# Environmental_PCB_Group5.net
KiCad netlist of a schematic drawn in EasyEDA Pro
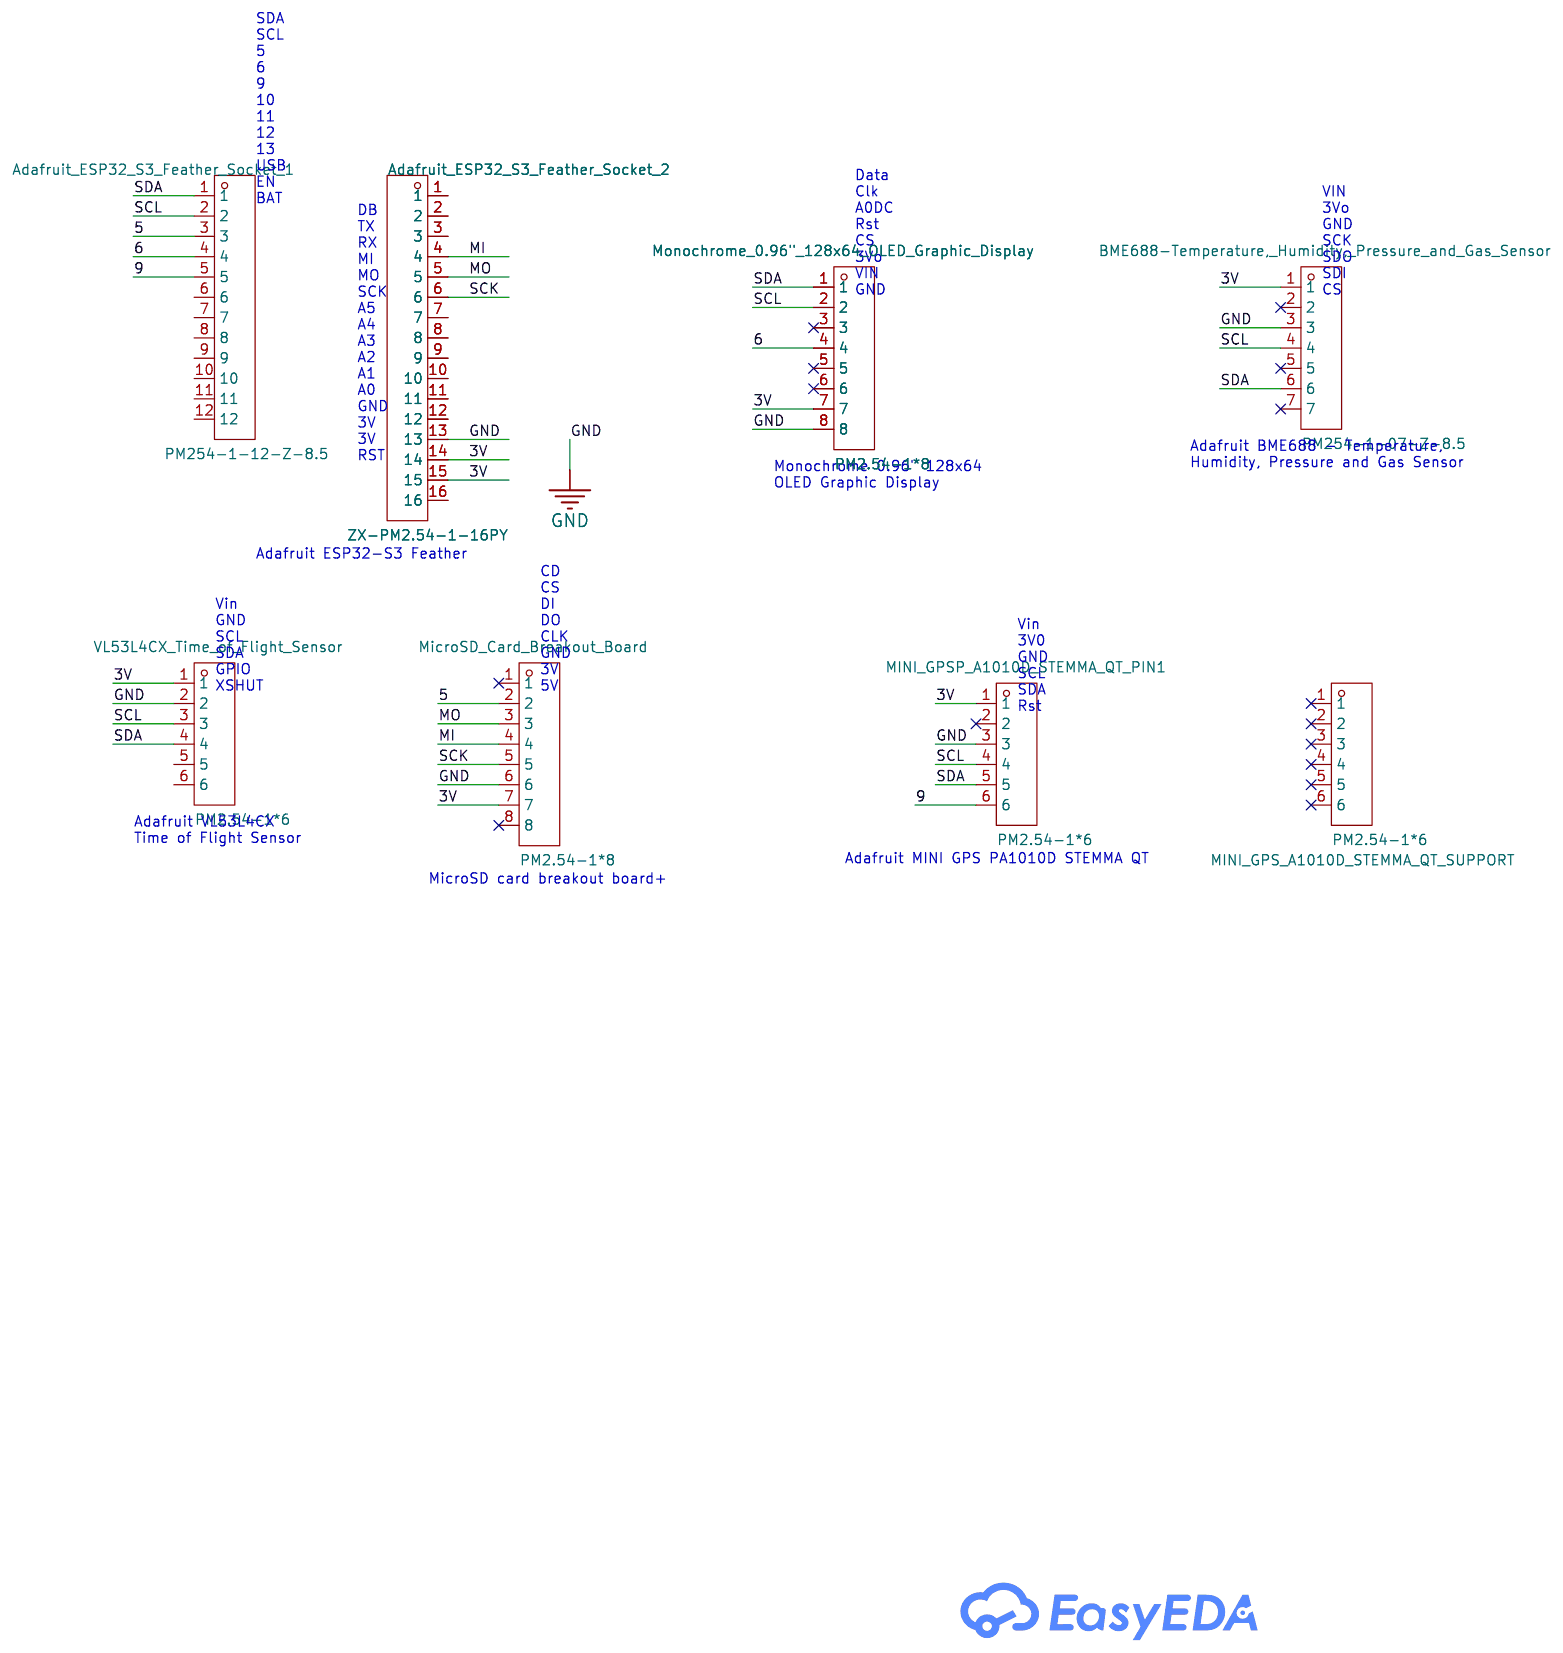
[diagram p0: schematic sheet]

(export (version "E")
  (design (tool "Eeschema 10.0.6"))
  (components
    (comp (ref "Adafruit_ESP32_S3_Feather_Socket_1")
      (value "PM254-1-12-Z-8.5")
      (footprint "easyedapro:HDR-TH_12P-P2.54-V-F")
      (fields (field (name "Manufacturer") "HCTL(华灿天禄)"))
      (libsource (lib "easyedapro") (part "PM254-1-12-Z-8.5"))
    )
    (comp (ref "Adafruit_ESP32_S3_Feather_Socket_2")
      (value "ZX-PM2.54-1-16PY")
      (footprint "easyedapro:HDR-TH_16P-P2.54-V-F-1")
      (fields (field (name "Manufacturer") "Megastar(兆星)"))
      (libsource (lib "easyedapro") (part "ZX-PM2.54-1-16PY"))
    )
    (comp (ref "BME688-Temperature,_Humidity,_Pressure_and_Gas_Sensor")
      (value "PM254-1-07-Z-8.5")
      (footprint "easyedapro:HDR-TH_7P-P2.54-V-F")
      (fields (field (name "Manufacturer") "HCTL(华灿天禄)"))
      (libsource (lib "easyedapro") (part "PM254-1-07-Z-8.5"))
    )
    (comp (ref "MicroSD_Card_Breakout_Board")
      (value "PM2.54-1*8")
      (footprint "easyedapro:HDR-TH_8P-P2.54-V-F")
      (fields (field (name "Manufacturer") "ZHOURI(洲日)"))
      (libsource (lib "easyedapro") (part "PM2.54-1*8"))
    )
    (comp (ref "MINI_GPSP_A1010D_STEMMA_QT_PIN1")
      (value "PM2.54-1*6")
      (footprint "easyedapro:HDR-TH_6P-P2.54-V-F_4")
      (fields (field (name "Manufacturer") "ZHOURI(洲日)"))
      (libsource (lib "easyedapro") (part "PM2.54-1*6"))
    )
    (comp (ref "MINI_GPS_A1010D_STEMMA_QT_SUPPORT")
      (value "PM2.54-1*6")
      (footprint "easyedapro:HDR-TH_6P-P2.54-V-F_4")
      (fields (field (name "Manufacturer") "ZHOURI(洲日)"))
      (libsource (lib "easyedapro") (part "PM2.54-1*6"))
    )
    (comp (ref "Monochrome_0.96\"_128x64_OLED_Graphic_Display")
      (value "PM2.54-1*8")
      (footprint "easyedapro:HDR-TH_8P-P2.54-V-F")
      (fields (field (name "Manufacturer") "ZHOURI(洲日)"))
      (libsource (lib "easyedapro") (part "PM2.54-1*8"))
    )
    (comp (ref "VL53L4CX_Time_of_Flight_Sensor")
      (value "PM2.54-1*6")
      (footprint "easyedapro:HDR-TH_6P-P2.54-V-F_4")
      (fields (field (name "Manufacturer") "ZHOURI(洲日)"))
      (libsource (lib "easyedapro") (part "PM2.54-1*6"))
    )
  )
  (nets
    (net (code "1") (name "/3V") (class "Default")
      (node (ref "Adafruit_ESP32_S3_Feather_Socket_2") (pin "14") (pinfunction "14_14") (pintype "unspecified"))
      (node (ref "Adafruit_ESP32_S3_Feather_Socket_2") (pin "15") (pinfunction "15_15") (pintype "unspecified"))
      (node (ref "BME688-Temperature,_Humidity,_Pressure_and_Gas_Sensor") (pin "1") (pinfunction "1_1") (pintype "unspecified"))
      (node (ref "MINI_GPSP_A1010D_STEMMA_QT_PIN1") (pin "1") (pinfunction "1_1") (pintype "unspecified"))
      (node (ref "MicroSD_Card_Breakout_Board") (pin "7") (pinfunction "7_7") (pintype "unspecified"))
      (node (ref "Monochrome_0.96\"_128x64_OLED_Graphic_Display") (pin "7") (pinfunction "7_7") (pintype "unspecified"))
      (node (ref "VL53L4CX_Time_of_Flight_Sensor") (pin "1") (pinfunction "1_1") (pintype "unspecified"))
    )
    (net (code "2") (name "/5") (class "Default")
      (node (ref "Adafruit_ESP32_S3_Feather_Socket_1") (pin "3") (pinfunction "3_3") (pintype "unspecified"))
      (node (ref "MicroSD_Card_Breakout_Board") (pin "2") (pinfunction "2_2") (pintype "unspecified"))
    )
    (net (code "3") (name "/6") (class "Default")
      (node (ref "Adafruit_ESP32_S3_Feather_Socket_1") (pin "4") (pinfunction "4_4") (pintype "unspecified"))
      (node (ref "Monochrome_0.96\"_128x64_OLED_Graphic_Display") (pin "4") (pinfunction "4_4") (pintype "unspecified"))
    )
    (net (code "4") (name "/9") (class "Default")
      (node (ref "Adafruit_ESP32_S3_Feather_Socket_1") (pin "5") (pinfunction "5_5") (pintype "unspecified"))
      (node (ref "MINI_GPSP_A1010D_STEMMA_QT_PIN1") (pin "6") (pinfunction "6_6") (pintype "unspecified"))
    )
    (net (code "5") (name "/MI") (class "Default")
      (node (ref "Adafruit_ESP32_S3_Feather_Socket_2") (pin "4") (pinfunction "4_4") (pintype "unspecified"))
      (node (ref "MicroSD_Card_Breakout_Board") (pin "4") (pinfunction "4_4") (pintype "unspecified"))
    )
    (net (code "6") (name "/MO") (class "Default")
      (node (ref "Adafruit_ESP32_S3_Feather_Socket_2") (pin "5") (pinfunction "5_5") (pintype "unspecified"))
      (node (ref "MicroSD_Card_Breakout_Board") (pin "3") (pinfunction "3_3") (pintype "unspecified"))
    )
    (net (code "7") (name "/SCK") (class "Default")
      (node (ref "Adafruit_ESP32_S3_Feather_Socket_2") (pin "6") (pinfunction "6_6") (pintype "unspecified"))
      (node (ref "MicroSD_Card_Breakout_Board") (pin "5") (pinfunction "5_5") (pintype "unspecified"))
    )
    (net (code "8") (name "/SCL") (class "Default")
      (node (ref "Adafruit_ESP32_S3_Feather_Socket_1") (pin "2") (pinfunction "2_2") (pintype "unspecified"))
      (node (ref "BME688-Temperature,_Humidity,_Pressure_and_Gas_Sensor") (pin "4") (pinfunction "4_4") (pintype "unspecified"))
      (node (ref "MINI_GPSP_A1010D_STEMMA_QT_PIN1") (pin "4") (pinfunction "4_4") (pintype "unspecified"))
      (node (ref "Monochrome_0.96\"_128x64_OLED_Graphic_Display") (pin "2") (pinfunction "2_2") (pintype "unspecified"))
      (node (ref "VL53L4CX_Time_of_Flight_Sensor") (pin "3") (pinfunction "3_3") (pintype "unspecified"))
    )
    (net (code "9") (name "/SDA") (class "Default")
      (node (ref "Adafruit_ESP32_S3_Feather_Socket_1") (pin "1") (pinfunction "1_1") (pintype "unspecified"))
      (node (ref "BME688-Temperature,_Humidity,_Pressure_and_Gas_Sensor") (pin "6") (pinfunction "6_6") (pintype "unspecified"))
      (node (ref "MINI_GPSP_A1010D_STEMMA_QT_PIN1") (pin "5") (pinfunction "5_5") (pintype "unspecified"))
      (node (ref "Monochrome_0.96\"_128x64_OLED_Graphic_Display") (pin "1") (pinfunction "1_1") (pintype "unspecified"))
      (node (ref "VL53L4CX_Time_of_Flight_Sensor") (pin "4") (pinfunction "4_4") (pintype "unspecified"))
    )
    (net (code "10") (name "GND") (class "Default")
      (node (ref "Adafruit_ESP32_S3_Feather_Socket_2") (pin "13") (pinfunction "13_13") (pintype "unspecified"))
      (node (ref "BME688-Temperature,_Humidity,_Pressure_and_Gas_Sensor") (pin "3") (pinfunction "3_3") (pintype "unspecified"))
      (node (ref "MINI_GPSP_A1010D_STEMMA_QT_PIN1") (pin "3") (pinfunction "3_3") (pintype "unspecified"))
      (node (ref "MicroSD_Card_Breakout_Board") (pin "6") (pinfunction "6_6") (pintype "unspecified"))
      (node (ref "Monochrome_0.96\"_128x64_OLED_Graphic_Display") (pin "8") (pinfunction "8_8") (pintype "unspecified"))
      (node (ref "VL53L4CX_Time_of_Flight_Sensor") (pin "2") (pinfunction "2_2") (pintype "unspecified"))
    )
    (net (code "11") (name "unconnected-(Adafruit_ESP32_S3_Feather_Socket_1-Pad6)") (class "Default")
      (node (ref "Adafruit_ESP32_S3_Feather_Socket_1") (pin "6") (pinfunction "6_6") (pintype "unspecified"))
    )
    (net (code "12") (name "unconnected-(Adafruit_ESP32_S3_Feather_Socket_1-Pad7)") (class "Default")
      (node (ref "Adafruit_ESP32_S3_Feather_Socket_1") (pin "7") (pinfunction "7_7") (pintype "unspecified"))
    )
    (net (code "13") (name "unconnected-(Adafruit_ESP32_S3_Feather_Socket_1-Pad8)") (class "Default")
      (node (ref "Adafruit_ESP32_S3_Feather_Socket_1") (pin "8") (pinfunction "8_8") (pintype "unspecified"))
    )
    (net (code "14") (name "unconnected-(Adafruit_ESP32_S3_Feather_Socket_1-Pad9)") (class "Default")
      (node (ref "Adafruit_ESP32_S3_Feather_Socket_1") (pin "9") (pinfunction "9_9") (pintype "unspecified"))
    )
    (net (code "15") (name "unconnected-(Adafruit_ESP32_S3_Feather_Socket_1-Pad10)") (class "Default")
      (node (ref "Adafruit_ESP32_S3_Feather_Socket_1") (pin "10") (pinfunction "10_10") (pintype "unspecified"))
    )
    (net (code "16") (name "unconnected-(Adafruit_ESP32_S3_Feather_Socket_1-Pad11)") (class "Default")
      (node (ref "Adafruit_ESP32_S3_Feather_Socket_1") (pin "11") (pinfunction "11_11") (pintype "unspecified"))
    )
    (net (code "17") (name "unconnected-(Adafruit_ESP32_S3_Feather_Socket_1-Pad12)") (class "Default")
      (node (ref "Adafruit_ESP32_S3_Feather_Socket_1") (pin "12") (pinfunction "12_12") (pintype "unspecified"))
    )
    (net (code "18") (name "unconnected-(Adafruit_ESP32_S3_Feather_Socket_2-Pad1)") (class "Default")
      (node (ref "Adafruit_ESP32_S3_Feather_Socket_2") (pin "1") (pinfunction "1_1") (pintype "unspecified"))
    )
    (net (code "19") (name "unconnected-(Adafruit_ESP32_S3_Feather_Socket_2-Pad2)") (class "Default")
      (node (ref "Adafruit_ESP32_S3_Feather_Socket_2") (pin "2") (pinfunction "2_2") (pintype "unspecified"))
    )
    (net (code "20") (name "unconnected-(Adafruit_ESP32_S3_Feather_Socket_2-Pad3)") (class "Default")
      (node (ref "Adafruit_ESP32_S3_Feather_Socket_2") (pin "3") (pinfunction "3_3") (pintype "unspecified"))
    )
    (net (code "21") (name "unconnected-(Adafruit_ESP32_S3_Feather_Socket_2-Pad7)") (class "Default")
      (node (ref "Adafruit_ESP32_S3_Feather_Socket_2") (pin "7") (pinfunction "7_7") (pintype "unspecified"))
    )
    (net (code "22") (name "unconnected-(Adafruit_ESP32_S3_Feather_Socket_2-Pad8)") (class "Default")
      (node (ref "Adafruit_ESP32_S3_Feather_Socket_2") (pin "8") (pinfunction "8_8") (pintype "unspecified"))
    )
    (net (code "23") (name "unconnected-(Adafruit_ESP32_S3_Feather_Socket_2-Pad9)") (class "Default")
      (node (ref "Adafruit_ESP32_S3_Feather_Socket_2") (pin "9") (pinfunction "9_9") (pintype "unspecified"))
    )
    (net (code "24") (name "unconnected-(Adafruit_ESP32_S3_Feather_Socket_2-Pad10)") (class "Default")
      (node (ref "Adafruit_ESP32_S3_Feather_Socket_2") (pin "10") (pinfunction "10_10") (pintype "unspecified"))
    )
    (net (code "25") (name "unconnected-(Adafruit_ESP32_S3_Feather_Socket_2-Pad11)") (class "Default")
      (node (ref "Adafruit_ESP32_S3_Feather_Socket_2") (pin "11") (pinfunction "11_11") (pintype "unspecified"))
    )
    (net (code "26") (name "unconnected-(Adafruit_ESP32_S3_Feather_Socket_2-Pad12)") (class "Default")
      (node (ref "Adafruit_ESP32_S3_Feather_Socket_2") (pin "12") (pinfunction "12_12") (pintype "unspecified"))
    )
    (net (code "27") (name "unconnected-(Adafruit_ESP32_S3_Feather_Socket_2-Pad16)") (class "Default")
      (node (ref "Adafruit_ESP32_S3_Feather_Socket_2") (pin "16") (pinfunction "16_16") (pintype "unspecified"))
    )
    (net (code "28") (name "unconnected-(BME688-Temperature,_Humidity,_Pressure_and_Gas_Sensor-Pad2)") (class "Default")
      (node (ref "BME688-Temperature,_Humidity,_Pressure_and_Gas_Sensor") (pin "2") (pinfunction "2_2") (pintype "unspecified+no_connect"))
    )
    (net (code "29") (name "unconnected-(BME688-Temperature,_Humidity,_Pressure_and_Gas_Sensor-Pad5)") (class "Default")
      (node (ref "BME688-Temperature,_Humidity,_Pressure_and_Gas_Sensor") (pin "5") (pinfunction "5_5") (pintype "unspecified+no_connect"))
    )
    (net (code "30") (name "unconnected-(BME688-Temperature,_Humidity,_Pressure_and_Gas_Sensor-Pad7)") (class "Default")
      (node (ref "BME688-Temperature,_Humidity,_Pressure_and_Gas_Sensor") (pin "7") (pinfunction "7_7") (pintype "unspecified+no_connect"))
    )
    (net (code "31") (name "unconnected-(MINI_GPSP_A1010D_STEMMA_QT_PIN1-Pad2)") (class "Default")
      (node (ref "MINI_GPSP_A1010D_STEMMA_QT_PIN1") (pin "2") (pinfunction "2_2") (pintype "unspecified+no_connect"))
    )
    (net (code "32") (name "unconnected-(MINI_GPS_A1010D_STEMMA_QT_SUPPORT-Pad1)") (class "Default")
      (node (ref "MINI_GPS_A1010D_STEMMA_QT_SUPPORT") (pin "1") (pinfunction "1_1") (pintype "unspecified+no_connect"))
    )
    (net (code "33") (name "unconnected-(MINI_GPS_A1010D_STEMMA_QT_SUPPORT-Pad2)") (class "Default")
      (node (ref "MINI_GPS_A1010D_STEMMA_QT_SUPPORT") (pin "2") (pinfunction "2_2") (pintype "unspecified+no_connect"))
    )
    (net (code "34") (name "unconnected-(MINI_GPS_A1010D_STEMMA_QT_SUPPORT-Pad3)") (class "Default")
      (node (ref "MINI_GPS_A1010D_STEMMA_QT_SUPPORT") (pin "3") (pinfunction "3_3") (pintype "unspecified+no_connect"))
    )
    (net (code "35") (name "unconnected-(MINI_GPS_A1010D_STEMMA_QT_SUPPORT-Pad4)") (class "Default")
      (node (ref "MINI_GPS_A1010D_STEMMA_QT_SUPPORT") (pin "4") (pinfunction "4_4") (pintype "unspecified+no_connect"))
    )
    (net (code "36") (name "unconnected-(MINI_GPS_A1010D_STEMMA_QT_SUPPORT-Pad5)") (class "Default")
      (node (ref "MINI_GPS_A1010D_STEMMA_QT_SUPPORT") (pin "5") (pinfunction "5_5") (pintype "unspecified+no_connect"))
    )
    (net (code "37") (name "unconnected-(MINI_GPS_A1010D_STEMMA_QT_SUPPORT-Pad6)") (class "Default")
      (node (ref "MINI_GPS_A1010D_STEMMA_QT_SUPPORT") (pin "6") (pinfunction "6_6") (pintype "unspecified+no_connect"))
    )
    (net (code "38") (name "unconnected-(MicroSD_Card_Breakout_Board-Pad1)") (class "Default")
      (node (ref "MicroSD_Card_Breakout_Board") (pin "1") (pinfunction "1_1") (pintype "unspecified+no_connect"))
    )
    (net (code "39") (name "unconnected-(MicroSD_Card_Breakout_Board-Pad8)") (class "Default")
      (node (ref "MicroSD_Card_Breakout_Board") (pin "8") (pinfunction "8_8") (pintype "unspecified+no_connect"))
    )
    (net (code "40") (name "unconnected-(Monochrome_0.96\"_128x64_OLED_Graphic_Display-Pad3)") (class "Default")
      (node (ref "Monochrome_0.96\"_128x64_OLED_Graphic_Display") (pin "3") (pinfunction "3_3") (pintype "unspecified+no_connect"))
    )
    (net (code "41") (name "unconnected-(Monochrome_0.96\"_128x64_OLED_Graphic_Display-Pad5)") (class "Default")
      (node (ref "Monochrome_0.96\"_128x64_OLED_Graphic_Display") (pin "5") (pinfunction "5_5") (pintype "unspecified+no_connect"))
    )
    (net (code "42") (name "unconnected-(Monochrome_0.96\"_128x64_OLED_Graphic_Display-Pad6)") (class "Default")
      (node (ref "Monochrome_0.96\"_128x64_OLED_Graphic_Display") (pin "6") (pinfunction "6_6") (pintype "unspecified+no_connect"))
    )
    (net (code "43") (name "unconnected-(VL53L4CX_Time_of_Flight_Sensor-Pad5)") (class "Default")
      (node (ref "VL53L4CX_Time_of_Flight_Sensor") (pin "5") (pinfunction "5_5") (pintype "unspecified"))
    )
    (net (code "44") (name "unconnected-(VL53L4CX_Time_of_Flight_Sensor-Pad6)") (class "Default")
      (node (ref "VL53L4CX_Time_of_Flight_Sensor") (pin "6") (pinfunction "6_6") (pintype "unspecified"))
    )
  )
)
